# Channel_B.net
KiCad netlist of a schematic drawn in Altium Designer
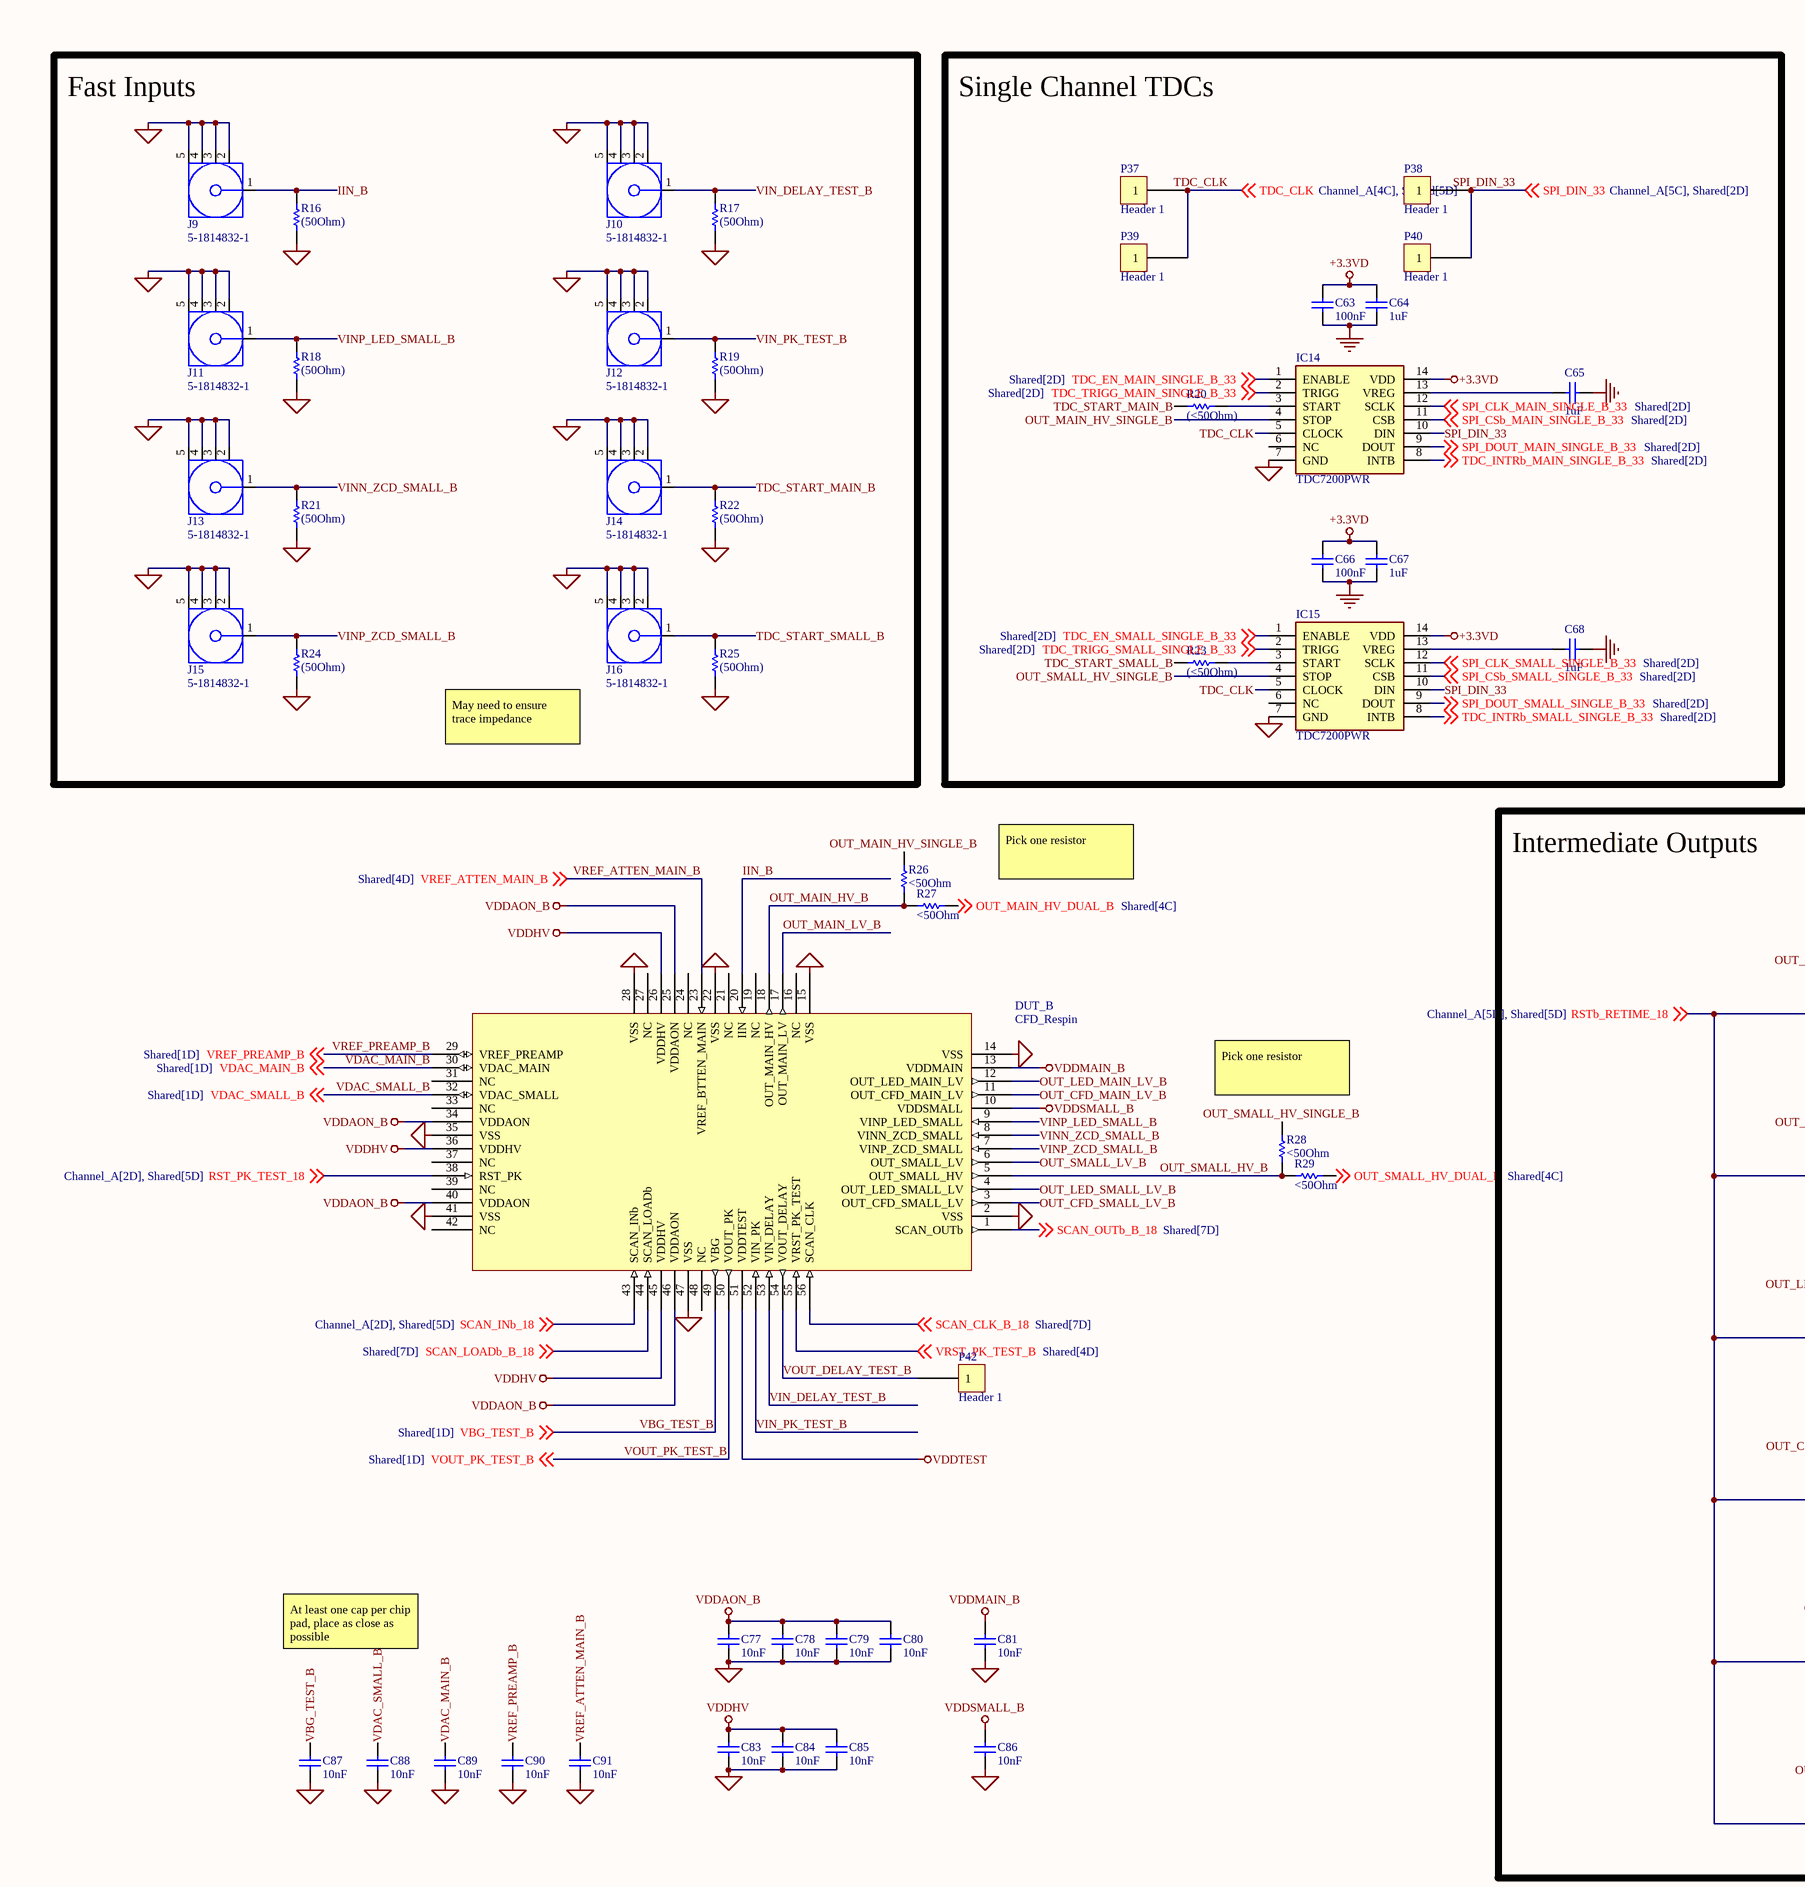
[diagram p0: Channel_B.SchDoc, left]
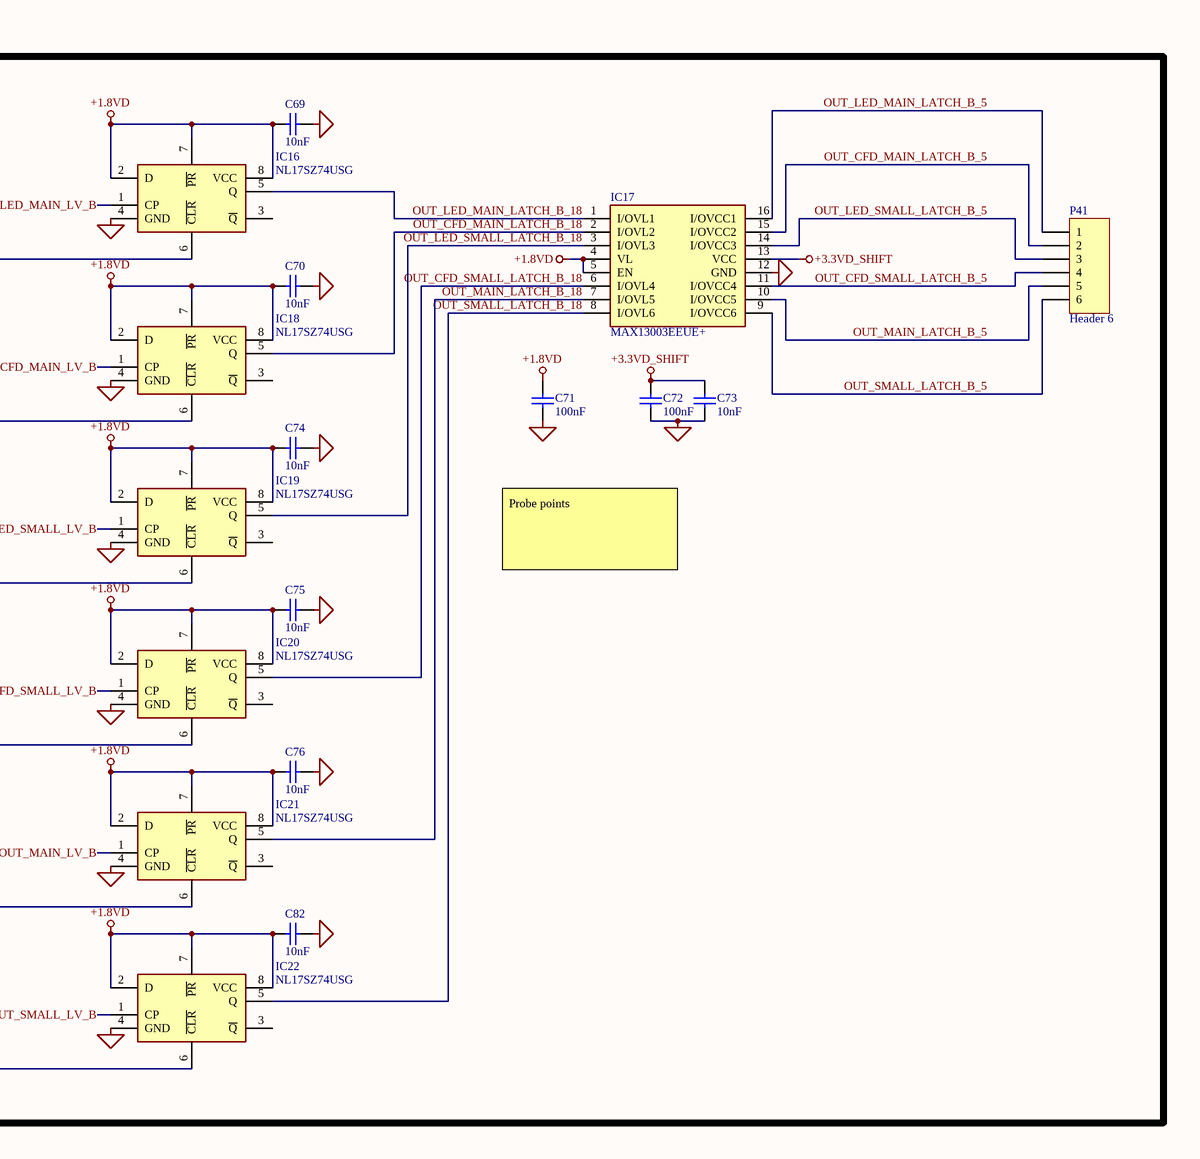
[diagram p1: Channel_B.SchDoc, right]

(export (version "E")
  (design (tool "Eeschema 10.0.6"))
  (components
    (comp (ref "C63")
      (value "100nF")
      (footprint "CAPC1608X90X35ML10T15")
      (description "0603")
      (fields (field (name "MANUFACTURER") "Murata"))
      (libsource (lib "Altium Content Vault") (part "CAP-NP-2"))
    )
    (comp (ref "C64")
      (value "1uF")
      (footprint "CAPC1608X90X35ML10T15")
      (description "0603")
      (fields (field (name "MANUFACTURER") "Murata"))
      (libsource (lib "Altium Content Vault") (part "CAP-NP-2"))
    )
    (comp (ref "C65")
      (value "1uF")
      (footprint "CAPC1608X90X35ML10T15")
      (description "0603")
      (fields (field (name "MANUFACTURER") "Murata"))
      (libsource (lib "Altium Content Vault") (part "CAP-NP-2"))
    )
    (comp (ref "C66")
      (value "100nF")
      (footprint "CAPC1608X90X35ML10T15")
      (description "0603")
      (fields (field (name "MANUFACTURER") "Murata"))
      (libsource (lib "Altium Content Vault") (part "CAP-NP-2"))
    )
    (comp (ref "C67")
      (value "1uF")
      (footprint "CAPC1608X90X35ML10T15")
      (description "0603")
      (fields (field (name "MANUFACTURER") "Murata"))
      (libsource (lib "Altium Content Vault") (part "CAP-NP-2"))
    )
    (comp (ref "C68")
      (value "1uF")
      (footprint "CAPC1608X90X35ML10T15")
      (description "0603")
      (fields (field (name "MANUFACTURER") "Murata"))
      (libsource (lib "Altium Content Vault") (part "CAP-NP-2"))
    )
    (comp (ref "C69")
      (value "10nF")
      (footprint "CAPC1608X90X35ML10T15")
      (description "0603")
      (fields (field (name "MANUFACTURER") "Murata"))
      (libsource (lib "Altium Content Vault") (part "CAP-NP-2"))
    )
    (comp (ref "C70")
      (value "10nF")
      (footprint "CAPC1608X90X35ML10T15")
      (description "0603")
      (fields (field (name "MANUFACTURER") "Murata"))
      (libsource (lib "Altium Content Vault") (part "CAP-NP-2"))
    )
    (comp (ref "C71")
      (value "100nF")
      (footprint "CAPC1608X90X35ML10T15")
      (description "0603")
      (fields (field (name "MANUFACTURER") "Murata"))
      (libsource (lib "Altium Content Vault") (part "CAP-NP-2"))
    )
    (comp (ref "C72")
      (value "100nF")
      (footprint "CAPC1608X90X35ML10T15")
      (description "0603")
      (fields (field (name "MANUFACTURER") "Murata"))
      (libsource (lib "Altium Content Vault") (part "CAP-NP-2"))
    )
    (comp (ref "C73")
      (value "10nF")
      (footprint "CAPC1608X90X35ML10T15")
      (description "0603")
      (fields (field (name "MANUFACTURER") "Murata"))
      (libsource (lib "Altium Content Vault") (part "CAP-NP-2"))
    )
    (comp (ref "C74")
      (value "10nF")
      (footprint "CAPC1608X90X35ML10T15")
      (description "0603")
      (fields (field (name "MANUFACTURER") "Murata"))
      (libsource (lib "Altium Content Vault") (part "CAP-NP-2"))
    )
    (comp (ref "C75")
      (value "10nF")
      (footprint "CAPC1608X90X35ML10T15")
      (description "0603")
      (fields (field (name "MANUFACTURER") "Murata"))
      (libsource (lib "Altium Content Vault") (part "CAP-NP-2"))
    )
    (comp (ref "C76")
      (value "10nF")
      (footprint "CAPC1608X90X35ML10T15")
      (description "0603")
      (fields (field (name "MANUFACTURER") "Murata"))
      (libsource (lib "Altium Content Vault") (part "CAP-NP-2"))
    )
    (comp (ref "C77")
      (value "10nF")
      (footprint "CAPC1608X90X35ML10T15")
      (description "0603")
      (fields (field (name "MANUFACTURER") "Murata"))
      (libsource (lib "Altium Content Vault") (part "CAP-NP-2"))
    )
    (comp (ref "C78")
      (value "10nF")
      (footprint "CAPC1608X90X35ML10T15")
      (description "0603")
      (fields (field (name "MANUFACTURER") "Murata"))
      (libsource (lib "Altium Content Vault") (part "CAP-NP-2"))
    )
    (comp (ref "C79")
      (value "10nF")
      (footprint "CAPC1608X90X35ML10T15")
      (description "0603")
      (fields (field (name "MANUFACTURER") "Murata"))
      (libsource (lib "Altium Content Vault") (part "CAP-NP-2"))
    )
    (comp (ref "C80")
      (value "10nF")
      (footprint "CAPC1608X90X35ML10T15")
      (description "0603")
      (fields (field (name "MANUFACTURER") "Murata"))
      (libsource (lib "Altium Content Vault") (part "CAP-NP-2"))
    )
    (comp (ref "C81")
      (value "10nF")
      (footprint "CAPC1608X90X35ML10T15")
      (description "0603")
      (fields (field (name "MANUFACTURER") "Murata"))
      (libsource (lib "Altium Content Vault") (part "CAP-NP-2"))
    )
    (comp (ref "C82")
      (value "10nF")
      (footprint "CAPC1608X90X35ML10T15")
      (description "0603")
      (fields (field (name "MANUFACTURER") "Murata"))
      (libsource (lib "Altium Content Vault") (part "CAP-NP-2"))
    )
    (comp (ref "C83")
      (value "10nF")
      (footprint "CAPC1608X90X35ML10T15")
      (description "0603")
      (fields (field (name "MANUFACTURER") "Murata"))
      (libsource (lib "Altium Content Vault") (part "CAP-NP-2"))
    )
    (comp (ref "C84")
      (value "10nF")
      (footprint "CAPC1608X90X35ML10T15")
      (description "0603")
      (fields (field (name "MANUFACTURER") "Murata"))
      (libsource (lib "Altium Content Vault") (part "CAP-NP-2"))
    )
    (comp (ref "C85")
      (value "10nF")
      (footprint "CAPC1608X90X35ML10T15")
      (description "0603")
      (fields (field (name "MANUFACTURER") "Murata"))
      (libsource (lib "Altium Content Vault") (part "CAP-NP-2"))
    )
    (comp (ref "C86")
      (value "10nF")
      (footprint "CAPC1608X90X35ML10T15")
      (description "0603")
      (fields (field (name "MANUFACTURER") "Murata"))
      (libsource (lib "Altium Content Vault") (part "CAP-NP-2"))
    )
    (comp (ref "C87")
      (value "10nF")
      (footprint "CAPC1608X90X35ML10T15")
      (description "0603")
      (fields (field (name "MANUFACTURER") "Murata"))
      (libsource (lib "Altium Content Vault") (part "CAP-NP-2"))
    )
    (comp (ref "C88")
      (value "10nF")
      (footprint "CAPC1608X90X35ML10T15")
      (description "0603")
      (fields (field (name "MANUFACTURER") "Murata"))
      (libsource (lib "Altium Content Vault") (part "CAP-NP-2"))
    )
    (comp (ref "C89")
      (value "10nF")
      (footprint "CAPC1608X90X35ML10T15")
      (description "0603")
      (fields (field (name "MANUFACTURER") "Murata"))
      (libsource (lib "Altium Content Vault") (part "CAP-NP-2"))
    )
    (comp (ref "C90")
      (value "10nF")
      (footprint "CAPC1608X90X35ML10T15")
      (description "0603")
      (fields (field (name "MANUFACTURER") "Murata"))
      (libsource (lib "Altium Content Vault") (part "CAP-NP-2"))
    )
    (comp (ref "C91")
      (value "10nF")
      (footprint "CAPC1608X90X35ML10T15")
      (description "0603")
      (fields (field (name "MANUFACTURER") "Murata"))
      (libsource (lib "Altium Content Vault") (part "CAP-NP-2"))
    )
    (comp (ref "DUT_B")
      (value "CFD_Respin")
      (footprint "QFN50P800X800X80_HS-57N_WIDEVIAS")
      (libsource (lib "intlib") (part "CFD_Respin"))
    )
    (comp (ref "IC14")
      (value "TDC7200PWR")
      (footprint "SamacSys:SOP65P640X120-14N")
      (description "Integrated Circuit")
      (libsource (lib "*") (part "TDC7200PWR"))
    )
    (comp (ref "IC15")
      (value "TDC7200PWR")
      (footprint "SamacSys:SOP65P640X120-14N")
      (description "Integrated Circuit")
      (libsource (lib "*") (part "TDC7200PWR"))
    )
    (comp (ref "IC16")
      (value "NL17SZ74USG")
      (footprint "SamacSys:SOP50P310X90-8N")
      (description "Flip Flops 1.65-5.5V CMOS Single D-Type")
      (libsource (lib "SamacSys") (part "NL17SZ74USG"))
    )
    (comp (ref "IC17")
      (value "MAX13003EEUE+")
      (footprint "SamacSys:SOP65P640X110-16N")
      (description "Integrated Circuit")
      (libsource (lib "*") (part "MAX13003EEUE+"))
    )
    (comp (ref "IC18")
      (value "NL17SZ74USG")
      (footprint "SamacSys:SOP50P310X90-8N")
      (description "Flip Flops 1.65-5.5V CMOS Single D-Type")
      (libsource (lib "SamacSys") (part "NL17SZ74USG"))
    )
    (comp (ref "IC19")
      (value "NL17SZ74USG")
      (footprint "SamacSys:SOP50P310X90-8N")
      (description "Flip Flops 1.65-5.5V CMOS Single D-Type")
      (libsource (lib "SamacSys") (part "NL17SZ74USG"))
    )
    (comp (ref "IC20")
      (value "NL17SZ74USG")
      (footprint "SamacSys:SOP50P310X90-8N")
      (description "Flip Flops 1.65-5.5V CMOS Single D-Type")
      (libsource (lib "SamacSys") (part "NL17SZ74USG"))
    )
    (comp (ref "IC21")
      (value "NL17SZ74USG")
      (footprint "SamacSys:SOP50P310X90-8N")
      (description "Flip Flops 1.65-5.5V CMOS Single D-Type")
      (libsource (lib "SamacSys") (part "NL17SZ74USG"))
    )
    (comp (ref "IC22")
      (value "NL17SZ74USG")
      (footprint "SamacSys:SOP50P310X90-8N")
      (description "Flip Flops 1.65-5.5V CMOS Single D-Type")
      (libsource (lib "SamacSys") (part "NL17SZ74USG"))
    )
    (comp (ref "J9")
      (value "5-1814832-1")
      (footprint "TECO-5-1814832-1_V")
      (fields (field (name "MANUFACTURER") "TE Connectivity"))
      (libsource (lib "Altium Content Vault") (part "CN-S-4F-RF5"))
    )
    (comp (ref "J10")
      (value "5-1814832-1")
      (footprint "TECO-5-1814832-1_V")
      (fields (field (name "MANUFACTURER") "TE Connectivity"))
      (libsource (lib "Altium Content Vault") (part "CN-S-4F-RF5"))
    )
    (comp (ref "J11")
      (value "5-1814832-1")
      (footprint "TECO-5-1814832-1_V")
      (fields (field (name "MANUFACTURER") "TE Connectivity"))
      (libsource (lib "Altium Content Vault") (part "CN-S-4F-RF5"))
    )
    (comp (ref "J12")
      (value "5-1814832-1")
      (footprint "TECO-5-1814832-1_V")
      (fields (field (name "MANUFACTURER") "TE Connectivity"))
      (libsource (lib "Altium Content Vault") (part "CN-S-4F-RF5"))
    )
    (comp (ref "J13")
      (value "5-1814832-1")
      (footprint "TECO-5-1814832-1_V")
      (fields (field (name "MANUFACTURER") "TE Connectivity"))
      (libsource (lib "Altium Content Vault") (part "CN-S-4F-RF5"))
    )
    (comp (ref "J14")
      (value "5-1814832-1")
      (footprint "TECO-5-1814832-1_V")
      (fields (field (name "MANUFACTURER") "TE Connectivity"))
      (libsource (lib "Altium Content Vault") (part "CN-S-4F-RF5"))
    )
    (comp (ref "J15")
      (value "5-1814832-1")
      (footprint "TECO-5-1814832-1_V")
      (fields (field (name "MANUFACTURER") "TE Connectivity"))
      (libsource (lib "Altium Content Vault") (part "CN-S-4F-RF5"))
    )
    (comp (ref "J16")
      (value "5-1814832-1")
      (footprint "TECO-5-1814832-1_V")
      (fields (field (name "MANUFACTURER") "TE Connectivity"))
      (libsource (lib "Altium Content Vault") (part "CN-S-4F-RF5"))
    )
    (comp (ref "P37") (value "Header 1") (footprint "Header1") (libsource (lib "intlib") (part "Header 1")))
    (comp (ref "P38") (value "Header 1") (footprint "Header1") (libsource (lib "intlib") (part "Header 1")))
    (comp (ref "P39") (value "Header 1") (footprint "Header1") (libsource (lib "intlib") (part "Header 1")))
    (comp (ref "P40") (value "Header 1") (footprint "Header1") (libsource (lib "intlib") (part "Header 1")))
    (comp (ref "P41")
      (value "Header 6")
      (footprint "HDR1X6")
      (description "Header, 6-Pin")
      (fields (field (name "PUBLISHER") "Altium Limited"))
      (libsource (lib "Miscellaneous Connectors") (part "Header 6"))
    )
    (comp (ref "P42") (value "Header 1") (footprint "Header1") (libsource (lib "") (part "Header 1_1")))
    (comp (ref "R16")
      (value "(50Ohm)")
      (footprint "RESC1609X50X30NL8T20")
      (description "0603")
      (fields (field (name "MANUFACTURER") "Vishay Semiconductor"))
      (libsource (lib "Altium Content Vault") (part "RES-2"))
    )
    (comp (ref "R17")
      (value "(50Ohm)")
      (footprint "RESC1609X50X30NL8T20")
      (description "0603")
      (fields (field (name "MANUFACTURER") "Vishay Semiconductor"))
      (libsource (lib "Altium Content Vault") (part "RES-2"))
    )
    (comp (ref "R18")
      (value "(50Ohm)")
      (footprint "RESC1609X50X30NL8T20")
      (description "0603")
      (fields (field (name "MANUFACTURER") "Vishay Semiconductor"))
      (libsource (lib "Altium Content Vault") (part "RES-2"))
    )
    (comp (ref "R19")
      (value "(50Ohm)")
      (footprint "RESC1609X50X30NL8T20")
      (description "0603")
      (fields (field (name "MANUFACTURER") "Vishay Semiconductor"))
      (libsource (lib "Altium Content Vault") (part "RES-2"))
    )
    (comp (ref "R20")
      (value "(<50Ohm)")
      (footprint "RESC1609X50X30NL8T20")
      (description "0603")
      (fields (field (name "MANUFACTURER") "Vishay Semiconductor"))
      (libsource (lib "Altium Content Vault") (part "RES-2"))
    )
    (comp (ref "R21")
      (value "(50Ohm)")
      (footprint "RESC1609X50X30NL8T20")
      (description "0603")
      (fields (field (name "MANUFACTURER") "Vishay Semiconductor"))
      (libsource (lib "Altium Content Vault") (part "RES-2"))
    )
    (comp (ref "R22")
      (value "(50Ohm)")
      (footprint "RESC1609X50X30NL8T20")
      (description "0603")
      (fields (field (name "MANUFACTURER") "Vishay Semiconductor"))
      (libsource (lib "Altium Content Vault") (part "RES-2"))
    )
    (comp (ref "R23")
      (value "(<50Ohm)")
      (footprint "RESC1609X50X30NL8T20")
      (description "0603")
      (fields (field (name "MANUFACTURER") "Vishay Semiconductor"))
      (libsource (lib "Altium Content Vault") (part "RES-2"))
    )
    (comp (ref "R24")
      (value "(50Ohm)")
      (footprint "RESC1609X50X30NL8T20")
      (description "0603")
      (fields (field (name "MANUFACTURER") "Vishay Semiconductor"))
      (libsource (lib "Altium Content Vault") (part "RES-2"))
    )
    (comp (ref "R25")
      (value "(50Ohm)")
      (footprint "RESC1609X50X30NL8T20")
      (description "0603")
      (fields (field (name "MANUFACTURER") "Vishay Semiconductor"))
      (libsource (lib "Altium Content Vault") (part "RES-2"))
    )
    (comp (ref "R26")
      (value "<50Ohm")
      (footprint "RESC1609X50X30NL8T20")
      (description "0603")
      (fields (field (name "MANUFACTURER") "Vishay Semiconductor"))
      (libsource (lib "Altium Content Vault") (part "RES-2"))
    )
    (comp (ref "R27")
      (value "<50Ohm")
      (footprint "RESC1609X50X30NL8T20")
      (description "0603")
      (fields (field (name "MANUFACTURER") "Vishay Semiconductor"))
      (libsource (lib "Altium Content Vault") (part "RES-2"))
    )
    (comp (ref "R28")
      (value "<50Ohm")
      (footprint "RESC1609X50X30NL8T20")
      (description "0603")
      (fields (field (name "MANUFACTURER") "Vishay Semiconductor"))
      (libsource (lib "Altium Content Vault") (part "RES-2"))
    )
    (comp (ref "R29")
      (value "<50Ohm")
      (footprint "RESC1609X50X30NL8T20")
      (description "0603")
      (fields (field (name "MANUFACTURER") "Vishay Semiconductor"))
      (libsource (lib "Altium Content Vault") (part "RES-2"))
    )
  )
  (nets
    (net (code "1") (name "+1.8VD") (class "Default")
      (node (ref "C69") (pin "2") (pinfunction "2_2") (pintype "passive"))
      (node (ref "C70") (pin "2") (pinfunction "2_2") (pintype "passive"))
      (node (ref "C71") (pin "2") (pinfunction "2_2") (pintype "passive"))
      (node (ref "C74") (pin "2") (pinfunction "2_2") (pintype "passive"))
      (node (ref "C75") (pin "2") (pinfunction "2_2") (pintype "passive"))
      (node (ref "C76") (pin "2") (pinfunction "2_2") (pintype "passive"))
      (node (ref "C82") (pin "2") (pinfunction "2_2") (pintype "passive"))
      (node (ref "IC16") (pin "2") (pinfunction "D_2") (pintype "passive"))
      (node (ref "IC16") (pin "7") (pinfunction "~{PR}_7") (pintype "passive"))
      (node (ref "IC16") (pin "8") (pinfunction "VCC_8") (pintype "passive"))
      (node (ref "IC17") (pin "4") (pinfunction "VL_4") (pintype "passive"))
      (node (ref "IC17") (pin "5") (pinfunction "EN_5") (pintype "passive"))
      (node (ref "IC18") (pin "2") (pinfunction "D_2") (pintype "passive"))
      (node (ref "IC18") (pin "7") (pinfunction "~{PR}_7") (pintype "passive"))
      (node (ref "IC18") (pin "8") (pinfunction "VCC_8") (pintype "passive"))
      (node (ref "IC19") (pin "2") (pinfunction "D_2") (pintype "passive"))
      (node (ref "IC19") (pin "7") (pinfunction "~{PR}_7") (pintype "passive"))
      (node (ref "IC19") (pin "8") (pinfunction "VCC_8") (pintype "passive"))
      (node (ref "IC20") (pin "2") (pinfunction "D_2") (pintype "passive"))
      (node (ref "IC20") (pin "7") (pinfunction "~{PR}_7") (pintype "passive"))
      (node (ref "IC20") (pin "8") (pinfunction "VCC_8") (pintype "passive"))
      (node (ref "IC21") (pin "2") (pinfunction "D_2") (pintype "passive"))
      (node (ref "IC21") (pin "7") (pinfunction "~{PR}_7") (pintype "passive"))
      (node (ref "IC21") (pin "8") (pinfunction "VCC_8") (pintype "passive"))
      (node (ref "IC22") (pin "2") (pinfunction "D_2") (pintype "passive"))
      (node (ref "IC22") (pin "7") (pinfunction "~{PR}_7") (pintype "passive"))
      (node (ref "IC22") (pin "8") (pinfunction "VCC_8") (pintype "passive"))
    )
    (net (code "2") (name "+3.3VD") (class "Default")
      (node (ref "C63") (pin "1") (pinfunction "1_1") (pintype "passive"))
      (node (ref "C64") (pin "1") (pinfunction "1_1") (pintype "passive"))
      (node (ref "C66") (pin "1") (pinfunction "1_1") (pintype "passive"))
      (node (ref "C67") (pin "1") (pinfunction "1_1") (pintype "passive"))
      (node (ref "IC14") (pin "14") (pinfunction "VDD_14") (pintype "passive"))
      (node (ref "IC15") (pin "14") (pinfunction "VDD_14") (pintype "passive"))
    )
    (net (code "3") (name "+3.3VD_SHIFT") (class "Default")
      (node (ref "C72") (pin "2") (pinfunction "2_2") (pintype "passive"))
      (node (ref "C73") (pin "2") (pinfunction "2_2") (pintype "passive"))
      (node (ref "IC17") (pin "13") (pinfunction "VCC_13") (pintype "passive"))
    )
    (net (code "4") (name "/IIN_B") (class "Default")
      (node (ref "DUT_B") (pin "20") (pinfunction "IIN_20") (pintype "input"))
      (node (ref "J9") (pin "1") (pinfunction "1_1") (pintype "passive"))
      (node (ref "R16") (pin "2") (pinfunction "2_2") (pintype "passive"))
    )
    (net (code "5") (name "/OUT_CFD_MAIN_LATCH_B_5") (class "Default")
      (node (ref "IC17") (pin "15") (pinfunction "I/OVCC2_15") (pintype "passive"))
      (node (ref "P41") (pin "2") (pinfunction "2_2") (pintype "passive"))
    )
    (net (code "6") (name "/OUT_CFD_MAIN_LATCH_B_18") (class "Default")
      (node (ref "IC17") (pin "2") (pinfunction "I/OVL2_2") (pintype "passive"))
      (node (ref "IC18") (pin "5") (pinfunction "Q_5") (pintype "passive"))
    )
    (net (code "7") (name "/OUT_CFD_MAIN_LV_B") (class "Default")
      (node (ref "DUT_B") (pin "11") (pinfunction "OUT_CFD_MAIN_LV_11") (pintype "output"))
      (node (ref "IC18") (pin "1") (pinfunction "CP_1") (pintype "passive"))
    )
    (net (code "8") (name "/OUT_CFD_SMALL_LATCH_B_5") (class "Default")
      (node (ref "IC17") (pin "11") (pinfunction "I/OVCC4_11") (pintype "passive"))
      (node (ref "P41") (pin "4") (pinfunction "4_4") (pintype "passive"))
    )
    (net (code "9") (name "/OUT_CFD_SMALL_LATCH_B_18") (class "Default")
      (node (ref "IC17") (pin "6") (pinfunction "I/OVL4_6") (pintype "passive"))
      (node (ref "IC20") (pin "5") (pinfunction "Q_5") (pintype "passive"))
    )
    (net (code "10") (name "/OUT_CFD_SMALL_LV_B") (class "Default")
      (node (ref "DUT_B") (pin "3") (pinfunction "OUT_CFD_SMALL_LV_3") (pintype "output"))
      (node (ref "IC20") (pin "1") (pinfunction "CP_1") (pintype "passive"))
    )
    (net (code "11") (name "/OUT_LED_MAIN_LATCH_B_5") (class "Default")
      (node (ref "IC17") (pin "16") (pinfunction "I/OVCC1_16") (pintype "passive"))
      (node (ref "P41") (pin "1") (pinfunction "1_1") (pintype "passive"))
    )
    (net (code "12") (name "/OUT_LED_MAIN_LATCH_B_18") (class "Default")
      (node (ref "IC16") (pin "5") (pinfunction "Q_5") (pintype "passive"))
      (node (ref "IC17") (pin "1") (pinfunction "I/OVL1_1") (pintype "passive"))
    )
    (net (code "13") (name "/OUT_LED_MAIN_LV_B") (class "Default")
      (node (ref "DUT_B") (pin "12") (pinfunction "OUT_LED_MAIN_LV_12") (pintype "output"))
      (node (ref "IC16") (pin "1") (pinfunction "CP_1") (pintype "passive"))
    )
    (net (code "14") (name "/OUT_LED_SMALL_LATCH_B_5") (class "Default")
      (node (ref "IC17") (pin "14") (pinfunction "I/OVCC3_14") (pintype "passive"))
      (node (ref "P41") (pin "3") (pinfunction "3_3") (pintype "passive"))
    )
    (net (code "15") (name "/OUT_LED_SMALL_LATCH_B_18") (class "Default")
      (node (ref "IC17") (pin "3") (pinfunction "I/OVL3_3") (pintype "passive"))
      (node (ref "IC19") (pin "5") (pinfunction "Q_5") (pintype "passive"))
    )
    (net (code "16") (name "/OUT_LED_SMALL_LV_B") (class "Default")
      (node (ref "DUT_B") (pin "4") (pinfunction "OUT_LED_SMALL_LV_4") (pintype "output"))
      (node (ref "IC19") (pin "1") (pinfunction "CP_1") (pintype "passive"))
    )
    (net (code "17") (name "/OUT_MAIN_HV_B") (class "Default")
      (node (ref "DUT_B") (pin "18") (pinfunction "OUT_MAIN_HV_18") (pintype "output"))
      (node (ref "R26") (pin "2") (pinfunction "2_2") (pintype "passive"))
      (node (ref "R27") (pin "1") (pinfunction "1_1") (pintype "passive"))
    )
    (net (code "18") (name "/OUT_MAIN_HV_SINGLE_B") (class "Default")
      (node (ref "IC14") (pin "4") (pinfunction "STOP_4") (pintype "passive"))
      (node (ref "R26") (pin "1") (pinfunction "1_1") (pintype "passive"))
    )
    (net (code "19") (name "/OUT_MAIN_LATCH_B_5") (class "Default")
      (node (ref "IC17") (pin "10") (pinfunction "I/OVCC5_10") (pintype "passive"))
      (node (ref "P41") (pin "5") (pinfunction "5_5") (pintype "passive"))
    )
    (net (code "20") (name "/OUT_MAIN_LATCH_B_18") (class "Default")
      (node (ref "IC17") (pin "7") (pinfunction "I/OVL5_7") (pintype "passive"))
      (node (ref "IC21") (pin "5") (pinfunction "Q_5") (pintype "passive"))
    )
    (net (code "21") (name "/OUT_MAIN_LV_B") (class "Default")
      (node (ref "DUT_B") (pin "17") (pinfunction "OUT_MAIN_LV_17") (pintype "output"))
      (node (ref "IC21") (pin "1") (pinfunction "CP_1") (pintype "passive"))
    )
    (net (code "22") (name "/OUT_SMALL_HV_B") (class "Default")
      (node (ref "DUT_B") (pin "5") (pinfunction "OUT_SMALL_HV_5") (pintype "output"))
      (node (ref "R28") (pin "2") (pinfunction "2_2") (pintype "passive"))
      (node (ref "R29") (pin "1") (pinfunction "1_1") (pintype "passive"))
    )
    (net (code "23") (name "/OUT_SMALL_HV_SINGLE_B") (class "Default")
      (node (ref "IC15") (pin "4") (pinfunction "STOP_4") (pintype "passive"))
      (node (ref "R28") (pin "1") (pinfunction "1_1") (pintype "passive"))
    )
    (net (code "24") (name "/OUT_SMALL_LATCH_B_5") (class "Default")
      (node (ref "IC17") (pin "9") (pinfunction "I/OVCC6_9") (pintype "passive"))
      (node (ref "P41") (pin "6") (pinfunction "6_6") (pintype "passive"))
    )
    (net (code "25") (name "/OUT_SMALL_LATCH_B_18") (class "Default")
      (node (ref "IC17") (pin "8") (pinfunction "I/OVL6_8") (pintype "passive"))
      (node (ref "IC22") (pin "5") (pinfunction "Q_5") (pintype "passive"))
    )
    (net (code "26") (name "/OUT_SMALL_LV_B") (class "Default")
      (node (ref "DUT_B") (pin "6") (pinfunction "OUT_SMALL_LV_6") (pintype "output"))
      (node (ref "IC22") (pin "1") (pinfunction "CP_1") (pintype "passive"))
    )
    (net (code "27") (name "/TDC_START_MAIN_B") (class "Default")
      (node (ref "J14") (pin "1") (pinfunction "1_1") (pintype "passive"))
      (node (ref "R20") (pin "1") (pinfunction "1_1") (pintype "passive"))
      (node (ref "R22") (pin "2") (pinfunction "2_2") (pintype "passive"))
    )
    (net (code "28") (name "/TDC_START_SMALL_B") (class "Default")
      (node (ref "J16") (pin "1") (pinfunction "1_1") (pintype "passive"))
      (node (ref "R23") (pin "1") (pinfunction "1_1") (pintype "passive"))
      (node (ref "R25") (pin "2") (pinfunction "2_2") (pintype "passive"))
    )
    (net (code "29") (name "/VINN_ZCD_SMALL_B") (class "Default")
      (node (ref "DUT_B") (pin "8") (pinfunction "VINN_ZCD_SMALL_8") (pintype "input"))
      (node (ref "J13") (pin "1") (pinfunction "1_1") (pintype "passive"))
      (node (ref "R21") (pin "2") (pinfunction "2_2") (pintype "passive"))
    )
    (net (code "30") (name "/VINP_LED_SMALL_B") (class "Default")
      (node (ref "DUT_B") (pin "9") (pinfunction "VINP_LED_SMALL_9") (pintype "input"))
      (node (ref "J11") (pin "1") (pinfunction "1_1") (pintype "passive"))
      (node (ref "R18") (pin "2") (pinfunction "2_2") (pintype "passive"))
    )
    (net (code "31") (name "/VINP_ZCD_SMALL_B") (class "Default")
      (node (ref "DUT_B") (pin "7") (pinfunction "VINP_ZCD_SMALL_7") (pintype "input"))
      (node (ref "J15") (pin "1") (pinfunction "1_1") (pintype "passive"))
      (node (ref "R24") (pin "2") (pinfunction "2_2") (pintype "passive"))
    )
    (net (code "32") (name "/VIN_DELAY_TEST_B") (class "Default")
      (node (ref "DUT_B") (pin "53") (pinfunction "VIN_DELAY_53") (pintype "input"))
      (node (ref "J10") (pin "1") (pinfunction "1_1") (pintype "passive"))
      (node (ref "R17") (pin "2") (pinfunction "2_2") (pintype "passive"))
    )
    (net (code "33") (name "/VIN_PK_TEST_B") (class "Default")
      (node (ref "DUT_B") (pin "52") (pinfunction "VIN_PK_52") (pintype "input"))
      (node (ref "J12") (pin "1") (pinfunction "1_1") (pintype "passive"))
      (node (ref "R19") (pin "2") (pinfunction "2_2") (pintype "passive"))
    )
    (net (code "34") (name "/VOUT_DELAY_TEST_B") (class "Default")
      (node (ref "DUT_B") (pin "54") (pinfunction "VOUT_DELAY_54") (pintype "output"))
      (node (ref "P42") (pin "1") (pinfunction "1_1") (pintype "passive"))
    )
    (net (code "35") (name "GND") (class "Default")
      (node (ref "C63") (pin "2") (pinfunction "2_2") (pintype "passive"))
      (node (ref "C64") (pin "2") (pinfunction "2_2") (pintype "passive"))
      (node (ref "C65") (pin "2") (pinfunction "2_2") (pintype "passive"))
      (node (ref "C66") (pin "2") (pinfunction "2_2") (pintype "passive"))
      (node (ref "C67") (pin "2") (pinfunction "2_2") (pintype "passive"))
      (node (ref "C68") (pin "2") (pinfunction "2_2") (pintype "passive"))
      (node (ref "C69") (pin "1") (pinfunction "1_1") (pintype "passive"))
      (node (ref "C70") (pin "1") (pinfunction "1_1") (pintype "passive"))
      (node (ref "C71") (pin "1") (pinfunction "1_1") (pintype "passive"))
      (node (ref "C72") (pin "1") (pinfunction "1_1") (pintype "passive"))
      (node (ref "C73") (pin "1") (pinfunction "1_1") (pintype "passive"))
      (node (ref "C74") (pin "1") (pinfunction "1_1") (pintype "passive"))
      (node (ref "C75") (pin "1") (pinfunction "1_1") (pintype "passive"))
      (node (ref "C76") (pin "1") (pinfunction "1_1") (pintype "passive"))
      (node (ref "C77") (pin "1") (pinfunction "1_1") (pintype "passive"))
      (node (ref "C78") (pin "1") (pinfunction "1_1") (pintype "passive"))
      (node (ref "C79") (pin "1") (pinfunction "1_1") (pintype "passive"))
      (node (ref "C80") (pin "1") (pinfunction "1_1") (pintype "passive"))
      (node (ref "C81") (pin "1") (pinfunction "1_1") (pintype "passive"))
      (node (ref "C82") (pin "1") (pinfunction "1_1") (pintype "passive"))
      (node (ref "C83") (pin "1") (pinfunction "1_1") (pintype "passive"))
      (node (ref "C84") (pin "1") (pinfunction "1_1") (pintype "passive"))
      (node (ref "C85") (pin "1") (pinfunction "1_1") (pintype "passive"))
      (node (ref "C86") (pin "1") (pinfunction "1_1") (pintype "passive"))
      (node (ref "C87") (pin "1") (pinfunction "1_1") (pintype "passive"))
      (node (ref "C88") (pin "1") (pinfunction "1_1") (pintype "passive"))
      (node (ref "C89") (pin "1") (pinfunction "1_1") (pintype "passive"))
      (node (ref "C90") (pin "1") (pinfunction "1_1") (pintype "passive"))
      (node (ref "C91") (pin "1") (pinfunction "1_1") (pintype "passive"))
      (node (ref "DUT_B") (pin "14") (pinfunction "VSS_14") (pintype "power_in"))
      (node (ref "DUT_B") (pin "15") (pinfunction "VSS_15") (pintype "power_in"))
      (node (ref "DUT_B") (pin "2") (pinfunction "VSS_2") (pintype "power_in"))
      (node (ref "DUT_B") (pin "22") (pinfunction "VSS_22") (pintype "power_in"))
      (node (ref "DUT_B") (pin "28") (pinfunction "VSS_28") (pintype "power_in"))
      (node (ref "DUT_B") (pin "35") (pinfunction "VSS_35") (pintype "power_in"))
      (node (ref "DUT_B") (pin "41") (pinfunction "VSS_41") (pintype "power_in"))
      (node (ref "DUT_B") (pin "47") (pinfunction "VSS_47") (pintype "power_in"))
      (node (ref "IC14") (pin "7") (pinfunction "GND_7") (pintype "passive"))
      (node (ref "IC15") (pin "7") (pinfunction "GND_7") (pintype "passive"))
      (node (ref "IC16") (pin "4") (pinfunction "GND_4") (pintype "passive"))
      (node (ref "IC17") (pin "12") (pinfunction "GND_12") (pintype "passive"))
      (node (ref "IC18") (pin "4") (pinfunction "GND_4") (pintype "passive"))
      (node (ref "IC19") (pin "4") (pinfunction "GND_4") (pintype "passive"))
      (node (ref "IC20") (pin "4") (pinfunction "GND_4") (pintype "passive"))
      (node (ref "IC21") (pin "4") (pinfunction "GND_4") (pintype "passive"))
      (node (ref "IC22") (pin "4") (pinfunction "GND_4") (pintype "passive"))
      (node (ref "J10") (pin "2") (pinfunction "2_2") (pintype "passive"))
      (node (ref "J10") (pin "3") (pinfunction "3_3") (pintype "passive"))
      (node (ref "J10") (pin "4") (pinfunction "4_4") (pintype "passive"))
      (node (ref "J10") (pin "5") (pinfunction "5_5") (pintype "passive"))
      (node (ref "J11") (pin "2") (pinfunction "2_2") (pintype "passive"))
      (node (ref "J11") (pin "3") (pinfunction "3_3") (pintype "passive"))
      (node (ref "J11") (pin "4") (pinfunction "4_4") (pintype "passive"))
      (node (ref "J11") (pin "5") (pinfunction "5_5") (pintype "passive"))
      (node (ref "J12") (pin "2") (pinfunction "2_2") (pintype "passive"))
      (node (ref "J12") (pin "3") (pinfunction "3_3") (pintype "passive"))
      (node (ref "J12") (pin "4") (pinfunction "4_4") (pintype "passive"))
      (node (ref "J12") (pin "5") (pinfunction "5_5") (pintype "passive"))
      (node (ref "J13") (pin "2") (pinfunction "2_2") (pintype "passive"))
      (node (ref "J13") (pin "3") (pinfunction "3_3") (pintype "passive"))
      (node (ref "J13") (pin "4") (pinfunction "4_4") (pintype "passive"))
      (node (ref "J13") (pin "5") (pinfunction "5_5") (pintype "passive"))
      (node (ref "J14") (pin "2") (pinfunction "2_2") (pintype "passive"))
      (node (ref "J14") (pin "3") (pinfunction "3_3") (pintype "passive"))
      (node (ref "J14") (pin "4") (pinfunction "4_4") (pintype "passive"))
      (node (ref "J14") (pin "5") (pinfunction "5_5") (pintype "passive"))
      (node (ref "J15") (pin "2") (pinfunction "2_2") (pintype "passive"))
      (node (ref "J15") (pin "3") (pinfunction "3_3") (pintype "passive"))
      (node (ref "J15") (pin "4") (pinfunction "4_4") (pintype "passive"))
      (node (ref "J15") (pin "5") (pinfunction "5_5") (pintype "passive"))
      (node (ref "J16") (pin "2") (pinfunction "2_2") (pintype "passive"))
      (node (ref "J16") (pin "3") (pinfunction "3_3") (pintype "passive"))
      (node (ref "J16") (pin "4") (pinfunction "4_4") (pintype "passive"))
      (node (ref "J16") (pin "5") (pinfunction "5_5") (pintype "passive"))
      (node (ref "J9") (pin "2") (pinfunction "2_2") (pintype "passive"))
      (node (ref "J9") (pin "3") (pinfunction "3_3") (pintype "passive"))
      (node (ref "J9") (pin "4") (pinfunction "4_4") (pintype "passive"))
      (node (ref "J9") (pin "5") (pinfunction "5_5") (pintype "passive"))
      (node (ref "R16") (pin "1") (pinfunction "1_1") (pintype "passive"))
      (node (ref "R17") (pin "1") (pinfunction "1_1") (pintype "passive"))
      (node (ref "R18") (pin "1") (pinfunction "1_1") (pintype "passive"))
      (node (ref "R19") (pin "1") (pinfunction "1_1") (pintype "passive"))
      (node (ref "R21") (pin "1") (pinfunction "1_1") (pintype "passive"))
      (node (ref "R22") (pin "1") (pinfunction "1_1") (pintype "passive"))
      (node (ref "R24") (pin "1") (pinfunction "1_1") (pintype "passive"))
      (node (ref "R25") (pin "1") (pinfunction "1_1") (pintype "passive"))
    )
    (net (code "36") (name "Net-(IC14-START)") (class "Default")
      (node (ref "IC14") (pin "3") (pinfunction "START_3") (pintype "passive"))
      (node (ref "R20") (pin "2") (pinfunction "2_2") (pintype "passive"))
    )
    (net (code "37") (name "Net-(IC14-VREG)") (class "Default")
      (node (ref "C65") (pin "1") (pinfunction "1_1") (pintype "passive"))
      (node (ref "IC14") (pin "13") (pinfunction "VREG_13") (pintype "passive"))
    )
    (net (code "38") (name "Net-(IC15-START)") (class "Default")
      (node (ref "IC15") (pin "3") (pinfunction "START_3") (pintype "passive"))
      (node (ref "R23") (pin "2") (pinfunction "2_2") (pintype "passive"))
    )
    (net (code "39") (name "Net-(IC15-VREG)") (class "Default")
      (node (ref "C68") (pin "1") (pinfunction "1_1") (pintype "passive"))
      (node (ref "IC15") (pin "13") (pinfunction "VREG_13") (pintype "passive"))
    )
    (net (code "40") (name "OUT_MAIN_HV_DUAL_B") (class "Default")
      (node (ref "R27") (pin "2") (pinfunction "2_2") (pintype "passive"))
    )
    (net (code "41") (name "OUT_SMALL_HV_DUAL_B") (class "Default")
      (node (ref "R29") (pin "2") (pinfunction "2_2") (pintype "passive"))
    )
    (net (code "42") (name "RST_PK_TEST_18") (class "Default")
      (node (ref "DUT_B") (pin "38") (pinfunction "RST_PK_38") (pintype "input"))
    )
    (net (code "43") (name "RSTb_RETIME_18") (class "Default")
      (node (ref "IC16") (pin "6") (pinfunction "~{CLR}_6") (pintype "passive"))
      (node (ref "IC18") (pin "6") (pinfunction "~{CLR}_6") (pintype "passive"))
      (node (ref "IC19") (pin "6") (pinfunction "~{CLR}_6") (pintype "passive"))
      (node (ref "IC20") (pin "6") (pinfunction "~{CLR}_6") (pintype "passive"))
      (node (ref "IC21") (pin "6") (pinfunction "~{CLR}_6") (pintype "passive"))
      (node (ref "IC22") (pin "6") (pinfunction "~{CLR}_6") (pintype "passive"))
    )
    (net (code "44") (name "SCAN_CLK_B_18") (class "Default")
      (node (ref "DUT_B") (pin "56") (pinfunction "SCAN_CLK_56") (pintype "input"))
    )
    (net (code "45") (name "SCAN_INb_18") (class "Default")
      (node (ref "DUT_B") (pin "43") (pinfunction "SCAN_INb_43") (pintype "input"))
    )
    (net (code "46") (name "SCAN_LOADb_B_18") (class "Default")
      (node (ref "DUT_B") (pin "44") (pinfunction "SCAN_LOADb_44") (pintype "input"))
    )
    (net (code "47") (name "SCAN_OUTb_B_18") (class "Default")
      (node (ref "DUT_B") (pin "1") (pinfunction "SCAN_OUTb_1") (pintype "output"))
    )
    (net (code "48") (name "SPI_CLK_MAIN_SINGLE_B_33") (class "Default")
      (node (ref "IC14") (pin "12") (pinfunction "SCLK_12") (pintype "passive"))
    )
    (net (code "49") (name "SPI_CLK_SMALL_SINGLE_B_33") (class "Default")
      (node (ref "IC15") (pin "12") (pinfunction "SCLK_12") (pintype "passive"))
    )
    (net (code "50") (name "SPI_CSb_MAIN_SINGLE_B_33") (class "Default")
      (node (ref "IC14") (pin "11") (pinfunction "CSB_11") (pintype "passive"))
    )
    (net (code "51") (name "SPI_CSb_SMALL_SINGLE_B_33") (class "Default")
      (node (ref "IC15") (pin "11") (pinfunction "CSB_11") (pintype "passive"))
    )
    (net (code "52") (name "SPI_DIN_33") (class "Default")
      (node (ref "IC14") (pin "10") (pinfunction "DIN_10") (pintype "passive"))
      (node (ref "IC15") (pin "10") (pinfunction "DIN_10") (pintype "passive"))
      (node (ref "P38") (pin "1") (pinfunction "1_1") (pintype "passive"))
      (node (ref "P40") (pin "1") (pinfunction "1_1") (pintype "passive"))
    )
    (net (code "53") (name "SPI_DOUT_MAIN_SINGLE_B_33") (class "Default")
      (node (ref "IC14") (pin "9") (pinfunction "DOUT_9") (pintype "passive"))
    )
    (net (code "54") (name "SPI_DOUT_SMALL_SINGLE_B_33") (class "Default")
      (node (ref "IC15") (pin "9") (pinfunction "DOUT_9") (pintype "passive"))
    )
    (net (code "55") (name "TDC_CLK") (class "Default")
      (node (ref "IC14") (pin "5") (pinfunction "CLOCK_5") (pintype "passive"))
      (node (ref "IC15") (pin "5") (pinfunction "CLOCK_5") (pintype "passive"))
      (node (ref "P37") (pin "1") (pinfunction "1_1") (pintype "passive"))
      (node (ref "P39") (pin "1") (pinfunction "1_1") (pintype "passive"))
    )
    (net (code "56") (name "TDC_EN_MAIN_SINGLE_B_33") (class "Default")
      (node (ref "IC14") (pin "1") (pinfunction "ENABLE_1") (pintype "passive"))
    )
    (net (code "57") (name "TDC_EN_SMALL_SINGLE_B_33") (class "Default")
      (node (ref "IC15") (pin "1") (pinfunction "ENABLE_1") (pintype "passive"))
    )
    (net (code "58") (name "TDC_INTRb_MAIN_SINGLE_B_33") (class "Default")
      (node (ref "IC14") (pin "8") (pinfunction "INTB_8") (pintype "passive"))
    )
    (net (code "59") (name "TDC_INTRb_SMALL_SINGLE_B_33") (class "Default")
      (node (ref "IC15") (pin "8") (pinfunction "INTB_8") (pintype "passive"))
    )
    (net (code "60") (name "TDC_TRIGG_MAIN_SINGLE_B_33") (class "Default")
      (node (ref "IC14") (pin "2") (pinfunction "TRIGG_2") (pintype "passive"))
    )
    (net (code "61") (name "TDC_TRIGG_SMALL_SINGLE_B_33") (class "Default")
      (node (ref "IC15") (pin "2") (pinfunction "TRIGG_2") (pintype "passive"))
    )
    (net (code "62") (name "VBG_TEST_B") (class "Default")
      (node (ref "C87") (pin "2") (pinfunction "2_2") (pintype "passive"))
      (node (ref "DUT_B") (pin "49") (pinfunction "VBG_49") (pintype "output"))
    )
    (net (code "63") (name "VDAC_MAIN_B") (class "Default")
      (node (ref "C89") (pin "2") (pinfunction "2_2") (pintype "passive"))
      (node (ref "DUT_B") (pin "30") (pinfunction "VDAC_MAIN_30") (pintype "bidirectional"))
    )
    (net (code "64") (name "VDAC_SMALL_B") (class "Default")
      (node (ref "C88") (pin "2") (pinfunction "2_2") (pintype "passive"))
      (node (ref "DUT_B") (pin "32") (pinfunction "VDAC_SMALL_32") (pintype "bidirectional"))
    )
    (net (code "65") (name "VDDAON_B") (class "Default")
      (node (ref "C77") (pin "2") (pinfunction "2_2") (pintype "passive"))
      (node (ref "C78") (pin "2") (pinfunction "2_2") (pintype "passive"))
      (node (ref "C79") (pin "2") (pinfunction "2_2") (pintype "passive"))
      (node (ref "C80") (pin "2") (pinfunction "2_2") (pintype "passive"))
      (node (ref "DUT_B") (pin "25") (pinfunction "VDDAON_25") (pintype "power_in"))
      (node (ref "DUT_B") (pin "34") (pinfunction "VDDAON_34") (pintype "power_in"))
      (node (ref "DUT_B") (pin "40") (pinfunction "VDDAON_40") (pintype "power_in"))
      (node (ref "DUT_B") (pin "46") (pinfunction "VDDAON_46") (pintype "power_in"))
    )
    (net (code "66") (name "VDDHV") (class "Default")
      (node (ref "C83") (pin "2") (pinfunction "2_2") (pintype "passive"))
      (node (ref "C84") (pin "2") (pinfunction "2_2") (pintype "passive"))
      (node (ref "C85") (pin "2") (pinfunction "2_2") (pintype "passive"))
      (node (ref "DUT_B") (pin "26") (pinfunction "VDDHV_26") (pintype "power_in"))
      (node (ref "DUT_B") (pin "36") (pinfunction "VDDHV_36") (pintype "power_in"))
      (node (ref "DUT_B") (pin "45") (pinfunction "VDDHV_45") (pintype "power_in"))
    )
    (net (code "67") (name "VDDMAIN_B") (class "Default")
      (node (ref "C81") (pin "2") (pinfunction "2_2") (pintype "passive"))
      (node (ref "DUT_B") (pin "13") (pinfunction "VDDMAIN_13") (pintype "power_in"))
    )
    (net (code "68") (name "VDDSMALL_B") (class "Default")
      (node (ref "C86") (pin "2") (pinfunction "2_2") (pintype "passive"))
      (node (ref "DUT_B") (pin "10") (pinfunction "VDDSMALL_10") (pintype "power_in"))
    )
    (net (code "69") (name "VDDTEST") (class "Default")
      (node (ref "DUT_B") (pin "51") (pinfunction "VDDTEST_51") (pintype "power_in"))
    )
    (net (code "70") (name "VOUT_PK_TEST_B") (class "Default")
      (node (ref "DUT_B") (pin "50") (pinfunction "VOUT_PK_50") (pintype "output"))
    )
    (net (code "71") (name "VREF_ATTEN_MAIN_B") (class "Default")
      (node (ref "C91") (pin "2") (pinfunction "2_2") (pintype "passive"))
      (node (ref "DUT_B") (pin "23") (pinfunction "VREF_BTTEN_MAIN_23") (pintype "input"))
    )
    (net (code "72") (name "VREF_PREAMP_B") (class "Default")
      (node (ref "C90") (pin "2") (pinfunction "2_2") (pintype "passive"))
      (node (ref "DUT_B") (pin "29") (pinfunction "VREF_PREAMP_29") (pintype "bidirectional"))
    )
    (net (code "73") (name "VRST_PK_TEST_B") (class "Default")
      (node (ref "DUT_B") (pin "55") (pinfunction "VRST_PK_TEST_55") (pintype "input"))
    )
    (net (code "74") (name "unconnected-(DUT_B-NC-Pad16)") (class "Default")
      (node (ref "DUT_B") (pin "16") (pinfunction "NC_16") (pintype "passive"))
    )
    (net (code "75") (name "unconnected-(DUT_B-NC-Pad19)") (class "Default")
      (node (ref "DUT_B") (pin "19") (pinfunction "NC_19") (pintype "passive"))
    )
    (net (code "76") (name "unconnected-(DUT_B-NC-Pad21)") (class "Default")
      (node (ref "DUT_B") (pin "21") (pinfunction "NC_21") (pintype "passive"))
    )
    (net (code "77") (name "unconnected-(DUT_B-NC-Pad24)") (class "Default")
      (node (ref "DUT_B") (pin "24") (pinfunction "NC_24") (pintype "passive"))
    )
    (net (code "78") (name "unconnected-(DUT_B-NC-Pad27)") (class "Default")
      (node (ref "DUT_B") (pin "27") (pinfunction "NC_27") (pintype "passive"))
    )
    (net (code "79") (name "unconnected-(DUT_B-NC-Pad31)") (class "Default")
      (node (ref "DUT_B") (pin "31") (pinfunction "NC_31") (pintype "passive"))
    )
    (net (code "80") (name "unconnected-(DUT_B-NC-Pad33)") (class "Default")
      (node (ref "DUT_B") (pin "33") (pinfunction "NC_33") (pintype "passive"))
    )
    (net (code "81") (name "unconnected-(DUT_B-NC-Pad37)") (class "Default")
      (node (ref "DUT_B") (pin "37") (pinfunction "NC_37") (pintype "passive"))
    )
    (net (code "82") (name "unconnected-(DUT_B-NC-Pad39)") (class "Default")
      (node (ref "DUT_B") (pin "39") (pinfunction "NC_39") (pintype "passive"))
    )
    (net (code "83") (name "unconnected-(DUT_B-NC-Pad42)") (class "Default")
      (node (ref "DUT_B") (pin "42") (pinfunction "NC_42") (pintype "passive"))
    )
    (net (code "84") (name "unconnected-(DUT_B-NC-Pad48)") (class "Default")
      (node (ref "DUT_B") (pin "48") (pinfunction "NC_48") (pintype "passive"))
    )
    (net (code "85") (name "unconnected-(IC14-NC-Pad6)") (class "Default")
      (node (ref "IC14") (pin "6") (pinfunction "NC_6") (pintype "passive"))
    )
    (net (code "86") (name "unconnected-(IC15-NC-Pad6)") (class "Default")
      (node (ref "IC15") (pin "6") (pinfunction "NC_6") (pintype "passive"))
    )
    (net (code "87") (name "unconnected-(IC16-~{Q}-Pad3)") (class "Default")
      (node (ref "IC16") (pin "3") (pinfunction "~{Q}_3") (pintype "passive"))
    )
    (net (code "88") (name "unconnected-(IC18-~{Q}-Pad3)") (class "Default")
      (node (ref "IC18") (pin "3") (pinfunction "~{Q}_3") (pintype "passive"))
    )
    (net (code "89") (name "unconnected-(IC19-~{Q}-Pad3)") (class "Default")
      (node (ref "IC19") (pin "3") (pinfunction "~{Q}_3") (pintype "passive"))
    )
    (net (code "90") (name "unconnected-(IC20-~{Q}-Pad3)") (class "Default")
      (node (ref "IC20") (pin "3") (pinfunction "~{Q}_3") (pintype "passive"))
    )
    (net (code "91") (name "unconnected-(IC21-~{Q}-Pad3)") (class "Default")
      (node (ref "IC21") (pin "3") (pinfunction "~{Q}_3") (pintype "passive"))
    )
    (net (code "92") (name "unconnected-(IC22-~{Q}-Pad3)") (class "Default")
      (node (ref "IC22") (pin "3") (pinfunction "~{Q}_3") (pintype "passive"))
    )
  )
)
